# biv2-batb_1a.net
KiCad netlist of a schematic drawn in Altium Designer
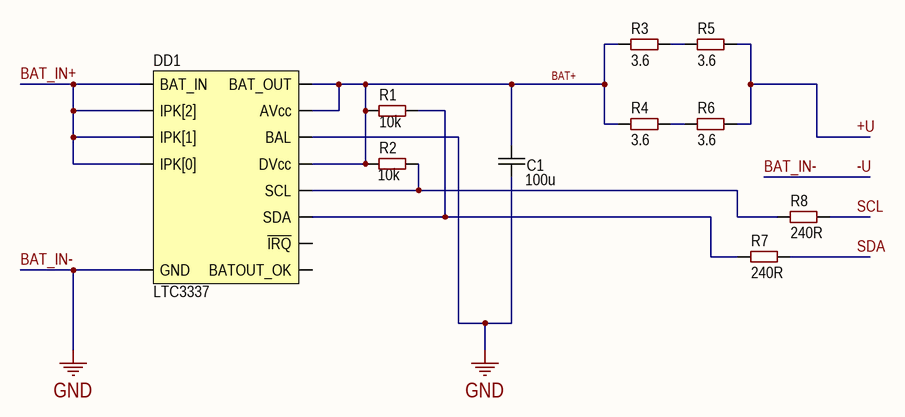
[diagram p0: biv2-batb_1a.SchDoc]

(export (version "E")
  (design (tool "Eeschema 10.0.6"))
  (components
    (comp (ref "C1")
      (value "100u")
      (footprint "CAP: 1206")
      (fields
        (field (name "MANUFACTURER") "Yageo")
        (field (name "PARTNUMBER") "CC1206KRX7R9BB104")
        (field (name "VALUEMANUFACTURERPARTNUMBER") "Ceramic capacitor, 100u, X7R, ±10%, 6V, 1206, -55...+125°C")
      )
      (libsource (lib "capacitor") (part "Ceramic_1206"))
    )
    (comp (ref "DD1")
      (value "LTC3337")
      (footprint "12-LFCSP")
      (description "Battery SOH monitor")
      (libsource (lib "ic-sensor") (part "LTC3337"))
    )
    (comp (ref "R1")
      (value "10k")
      (footprint "RES: 0402")
      (fields
        (field (name "MANUFACTURER") "Yageo")
        (field (name "PARTNUMBER") "RC0402JR-07100RL")
        (field (name "VALUEMANUFACTURERPARTNUMBER") "Resistor film, 10k, , 0402, 0.063W, -55...+125°C")
      )
      (libsource (lib "resistor") (part "Resistor_0402"))
    )
    (comp (ref "R2")
      (value "10k")
      (footprint "RES: 0402")
      (fields
        (field (name "MANUFACTURER") "Yageo")
        (field (name "PARTNUMBER") "RC0402JR-07100RL")
        (field (name "VALUEMANUFACTURERPARTNUMBER") "Resistor film, 10k, , 0402, 0.063W, -55...+125°C")
      )
      (libsource (lib "resistor") (part "Resistor_0402"))
    )
    (comp (ref "R3")
      (value "3.6")
      (footprint "RES: 2512")
      (fields
        (field (name "MANUFACTURER") "Yageo")
        (field (name "PARTNUMBER") "RC2512JK-07100RL")
        (field (name "VALUEMANUFACTURERPARTNUMBER") "Resistor film, 3.6, ±5%, 2512, 1W, -55...+125°C")
      )
      (libsource (lib "resistor") (part "Resistor_2512"))
    )
    (comp (ref "R4")
      (value "3.6")
      (footprint "RES: 2512")
      (fields
        (field (name "MANUFACTURER") "Yageo")
        (field (name "PARTNUMBER") "RC2512JK-07100RL")
        (field (name "VALUEMANUFACTURERPARTNUMBER") "Resistor film, 3.6, ±5%, 2512, 1W, -55...+125°C")
      )
      (libsource (lib "resistor") (part "Resistor_2512"))
    )
    (comp (ref "R5")
      (value "3.6")
      (footprint "RES: 2512")
      (fields
        (field (name "MANUFACTURER") "Yageo")
        (field (name "PARTNUMBER") "RC2512JK-07100RL")
        (field (name "VALUEMANUFACTURERPARTNUMBER") "Resistor film, 3.6, ±5%, 2512, 1W, -55...+125°C")
      )
      (libsource (lib "resistor") (part "Resistor_2512"))
    )
    (comp (ref "R6")
      (value "3.6")
      (footprint "RES: 2512")
      (fields
        (field (name "MANUFACTURER") "Yageo")
        (field (name "PARTNUMBER") "RC2512JK-07100RL")
        (field (name "VALUEMANUFACTURERPARTNUMBER") "Resistor film, 3.6, ±5%, 2512, 1W, -55...+125°C")
      )
      (libsource (lib "resistor") (part "Resistor_2512"))
    )
    (comp (ref "R7")
      (value "240R")
      (footprint "RES: 0603")
      (fields
        (field (name "MANUFACTURER") "Yageo")
        (field (name "PARTNUMBER") "RC0603JR-07100RL")
        (field (name "VALUEMANUFACTURERPARTNUMBER") "Resistor film, 240R, ±5%, 0603, 0.1W, -55...+125°C")
      )
      (libsource (lib "resistor") (part "Resistor_0603"))
    )
    (comp (ref "R8")
      (value "240R")
      (footprint "RES: 0603")
      (fields
        (field (name "MANUFACTURER") "Yageo")
        (field (name "PARTNUMBER") "RC0603JR-07100RL")
        (field (name "VALUEMANUFACTURERPARTNUMBER") "Resistor film, 240R, ±5%, 0603, 0.1W, -55...+125°C")
      )
      (libsource (lib "resistor") (part "Resistor_0603"))
    )
  )
  (nets
    (net (code "1") (name "/+U") (class "Default")
      (node (ref "R5") (pin "2") (pinfunction "2_2") (pintype "passive"))
      (node (ref "R6") (pin "2") (pinfunction "2_2") (pintype "passive"))
    )
    (net (code "2") (name "/BAT+") (class "Default")
      (node (ref "C1") (pin "2") (pinfunction "2_2") (pintype "passive"))
      (node (ref "DD1") (pin "12") (pinfunction "BAT_OUT_12") (pintype "passive"))
      (node (ref "DD1") (pin "2") (pinfunction "AVcc_2") (pintype "power_in"))
      (node (ref "DD1") (pin "3") (pinfunction "DVcc_3") (pintype "power_in"))
      (node (ref "R1") (pin "1") (pinfunction "1_1") (pintype "passive"))
      (node (ref "R2") (pin "1") (pinfunction "1_1") (pintype "passive"))
      (node (ref "R3") (pin "1") (pinfunction "1_1") (pintype "passive"))
      (node (ref "R4") (pin "1") (pinfunction "1_1") (pintype "passive"))
    )
    (net (code "3") (name "/BAT_IN+") (class "Default")
      (node (ref "DD1") (pin "10") (pinfunction "IPK[0]_10") (pintype "passive"))
      (node (ref "DD1") (pin "11") (pinfunction "BAT_IN_11") (pintype "passive"))
      (node (ref "DD1") (pin "8") (pinfunction "IPK[2]_8") (pintype "passive"))
      (node (ref "DD1") (pin "9") (pinfunction "IPK[1]_9") (pintype "passive"))
    )
    (net (code "4") (name "/SCL") (class "Default")
      (node (ref "R8") (pin "2") (pinfunction "2_2") (pintype "passive"))
    )
    (net (code "5") (name "/SDA") (class "Default")
      (node (ref "R7") (pin "2") (pinfunction "2_2") (pintype "passive"))
    )
    (net (code "6") (name "GND") (class "Default")
      (node (ref "C1") (pin "1") (pinfunction "1_1") (pintype "passive"))
      (node (ref "DD1") (pin "1") (pinfunction "BAL_1") (pintype "power_in"))
      (node (ref "DD1") (pin "13") (pinfunction "GND_13") (pintype "power_in"))
    )
    (net (code "7") (name "Net-(DD1-SCL)") (class "Default")
      (node (ref "DD1") (pin "4") (pinfunction "SCL_4") (pintype "power_in"))
      (node (ref "R2") (pin "2") (pinfunction "2_2") (pintype "passive"))
      (node (ref "R8") (pin "1") (pinfunction "1_1") (pintype "passive"))
    )
    (net (code "8") (name "Net-(DD1-SDA)") (class "Default")
      (node (ref "DD1") (pin "5") (pinfunction "SDA_5") (pintype "power_in"))
      (node (ref "R1") (pin "2") (pinfunction "2_2") (pintype "passive"))
      (node (ref "R7") (pin "1") (pinfunction "1_1") (pintype "passive"))
    )
    (net (code "9") (name "Net-(R3-Pad2)") (class "Default")
      (node (ref "R3") (pin "2") (pinfunction "2_2") (pintype "passive"))
      (node (ref "R5") (pin "1") (pinfunction "1_1") (pintype "passive"))
    )
    (net (code "10") (name "Net-(R4-Pad2)") (class "Default")
      (node (ref "R4") (pin "2") (pinfunction "2_2") (pintype "passive"))
      (node (ref "R6") (pin "1") (pinfunction "1_1") (pintype "passive"))
    )
    (net (code "11") (name "unconnected-(DD1-BATOUT_OK-Pad7)") (class "Default")
      (node (ref "DD1") (pin "7") (pinfunction "BATOUT_OK_7") (pintype "power_in"))
    )
    (net (code "12") (name "unconnected-(DD1-~{IRQ}-Pad6)") (class "Default")
      (node (ref "DD1") (pin "6") (pinfunction "~{IRQ}_6") (pintype "power_in"))
    )
  )
)
